# a718-noise-source.net
KiCad netlist of a schematic drawn in EAGLE
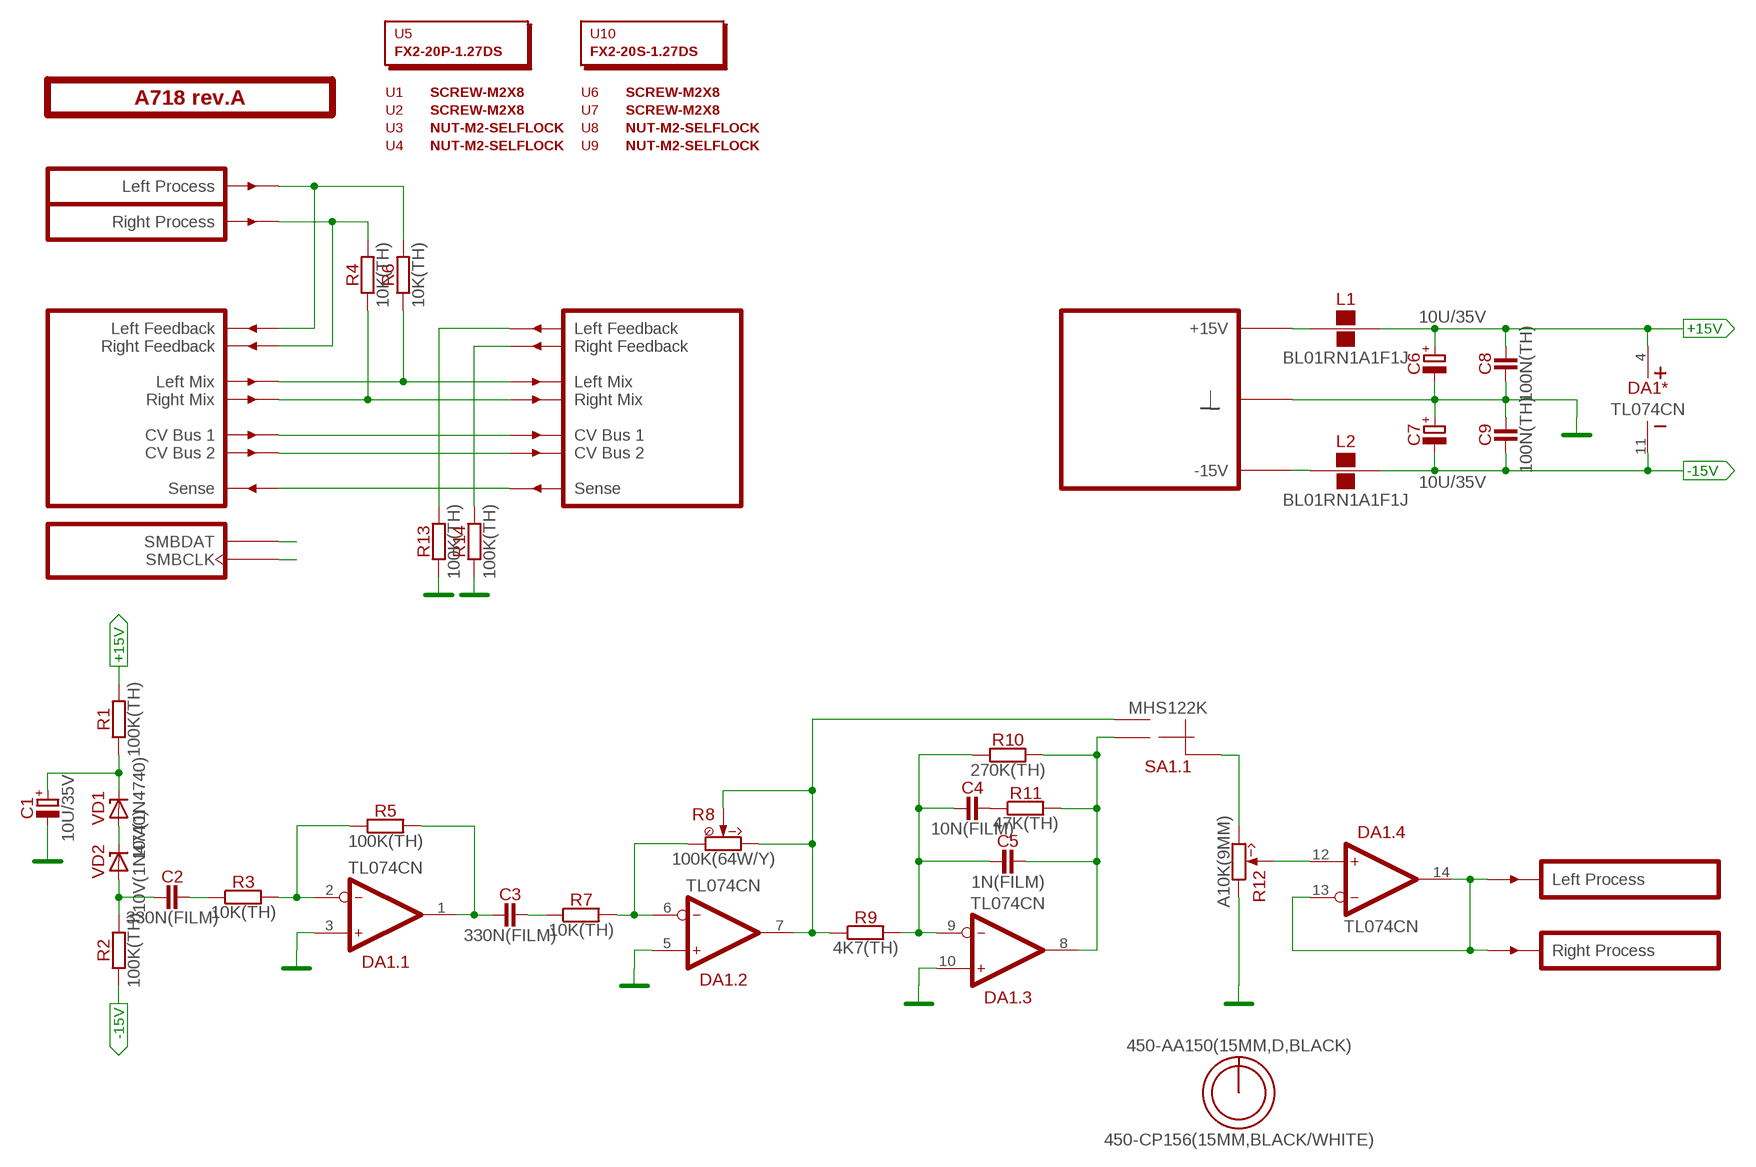
[diagram p0: schematic, sheet 1]

(export (version "E")
  (design (tool "Eeschema 10.0.6"))
  (components
    (comp (ref "C1")
      (value "10U/35V")
      (footprint "eagle-import:E2-5")
      (libsource (lib "eagle-import") (part "?10U/35V"))
    )
    (comp (ref "C2")
      (value "330N(FILM)")
      (footprint "eagle-import:C050-035X075")
      (libsource (lib "eagle-import") (part "?330N(FILM)"))
    )
    (comp (ref "C3")
      (value "330N(FILM)")
      (footprint "eagle-import:C050-035X075")
      (libsource (lib "eagle-import") (part "?330N(FILM)"))
    )
    (comp (ref "C4")
      (value "10N(FILM)")
      (footprint "eagle-import:C050-025X075")
      (libsource (lib "eagle-import") (part "?10N(FILM)"))
    )
    (comp (ref "C5")
      (value "1N(FILM)")
      (footprint "eagle-import:C050-025X075")
      (libsource (lib "eagle-import") (part "?1N(FILM)"))
    )
    (comp (ref "C6")
      (value "10U/35V")
      (footprint "eagle-import:E2-5")
      (libsource (lib "eagle-import") (part "?10U/35V"))
    )
    (comp (ref "C7")
      (value "10U/35V")
      (footprint "eagle-import:E2-5")
      (libsource (lib "eagle-import") (part "?10U/35V"))
    )
    (comp (ref "C8")
      (value "100N(TH)")
      (footprint "eagle-import:C050-024X044")
      (libsource (lib "eagle-import") (part "?100N(TH)"))
    )
    (comp (ref "C9")
      (value "100N(TH)")
      (footprint "eagle-import:C050-024X044")
      (libsource (lib "eagle-import") (part "?100N(TH)"))
    )
    (comp (ref "DA1")
      (value "TL074CN")
      (footprint "eagle-import:DIP-14")
      (libsource (lib "eagle-import") (part "TL074CN"))
    )
    (comp (ref "L1")
      (value "BL01RN1A1F1J")
      (footprint "eagle-import:BL01RN1A")
      (libsource (lib "eagle-import") (part "BL01RN1A?1F1J"))
    )
    (comp (ref "L2")
      (value "BL01RN1A1F1J")
      (footprint "eagle-import:BL01RN1A")
      (libsource (lib "eagle-import") (part "BL01RN1A?1F1J"))
    )
    (comp (ref "O1")
      (value "450-AA150(15MM,D,BLACK)")
      (footprint "eagle-import:EMPTY")
      (libsource (lib "eagle-import") (part "450-AA?150(15MM,D,BLACK)"))
    )
    (comp (ref "O2")
      (value "450-CP156(15MM,BLACK/WHITE)")
      (footprint "eagle-import:EMPTY")
      (libsource (lib "eagle-import") (part "450-C?P156(15MM,BLACK/WHITE)"))
    )
    (comp (ref "PCB1")
      (value "A718 rev.A")
      (footprint "eagle-import:ST2-BOARD-50")
      (libsource (lib "eagle-import") (part "ST2-BOARD-?50"))
    )
    (comp (ref "R1")
      (value "100K(TH)")
      (footprint "eagle-import:R-0207_10")
      (libsource (lib "eagle-import") (part "?100K(TH)"))
    )
    (comp (ref "R2")
      (value "100K(TH)")
      (footprint "eagle-import:R-0207_10")
      (libsource (lib "eagle-import") (part "?100K(TH)"))
    )
    (comp (ref "R3")
      (value "10K(TH)")
      (footprint "eagle-import:R-0207_10")
      (libsource (lib "eagle-import") (part "?10K(TH)"))
    )
    (comp (ref "R4")
      (value "10K(TH)")
      (footprint "eagle-import:R-0207_10")
      (libsource (lib "eagle-import") (part "?10K(TH)"))
    )
    (comp (ref "R5")
      (value "100K(TH)")
      (footprint "eagle-import:R-0207_10")
      (libsource (lib "eagle-import") (part "?100K(TH)"))
    )
    (comp (ref "R6")
      (value "10K(TH)")
      (footprint "eagle-import:R-0207_10")
      (libsource (lib "eagle-import") (part "?10K(TH)"))
    )
    (comp (ref "R7")
      (value "10K(TH)")
      (footprint "eagle-import:R-0207_10")
      (libsource (lib "eagle-import") (part "?10K(TH)"))
    )
    (comp (ref "R8")
      (value "100K(64W/Y)")
      (footprint "eagle-import:64W")
      (libsource (lib "eagle-import") (part "?(64W/Y)100K"))
    )
    (comp (ref "R9")
      (value "4K7(TH)")
      (footprint "eagle-import:R-0207_10")
      (libsource (lib "eagle-import") (part "?4K7(TH)"))
    )
    (comp (ref "R10")
      (value "270K(TH)")
      (footprint "eagle-import:R-0207_10")
      (libsource (lib "eagle-import") (part "?270K(TH)"))
    )
    (comp (ref "R11")
      (value "47K(TH)")
      (footprint "eagle-import:R-0207_10")
      (libsource (lib "eagle-import") (part "?47K(TH)"))
    )
    (comp (ref "R12")
      (value "A10K(9MM)")
      (footprint "eagle-import:RV09-SINGLE")
      (libsource (lib "eagle-import") (part "?A10K(9MM)"))
    )
    (comp (ref "R13")
      (value "100K(TH)")
      (footprint "eagle-import:R-0207_10")
      (libsource (lib "eagle-import") (part "?100K(TH)"))
    )
    (comp (ref "R14")
      (value "100K(TH)")
      (footprint "eagle-import:R-0207_10")
      (libsource (lib "eagle-import") (part "?100K(TH)"))
    )
    (comp (ref "SA1")
      (value "MHS122K")
      (footprint "eagle-import:APEM-MHS122K")
      (libsource (lib "eagle-import") (part "MHS122K"))
    )
    (comp (ref "U1")
      (value "SCREW-M2X8")
      (footprint "eagle-import:EMPTY")
      (libsource (lib "eagle-import") (part "?SCREW-M2X8"))
    )
    (comp (ref "U2")
      (value "SCREW-M2X8")
      (footprint "eagle-import:EMPTY")
      (libsource (lib "eagle-import") (part "?SCREW-M2X8"))
    )
    (comp (ref "U3")
      (value "NUT-M2-SELFLOCK")
      (footprint "eagle-import:EMPTY")
      (libsource (lib "eagle-import") (part "?NUT-M2-SELFLOCK"))
    )
    (comp (ref "U4")
      (value "NUT-M2-SELFLOCK")
      (footprint "eagle-import:EMPTY")
      (libsource (lib "eagle-import") (part "?NUT-M2-SELFLOCK"))
    )
    (comp (ref "U5")
      (value "FX2-20P-1.27DS")
      (footprint "eagle-import:EMPTY")
      (libsource (lib "eagle-import") (part "?FX2-20P-1.27DS"))
    )
    (comp (ref "U6")
      (value "SCREW-M2X8")
      (footprint "eagle-import:EMPTY")
      (libsource (lib "eagle-import") (part "?SCREW-M2X8"))
    )
    (comp (ref "U7")
      (value "SCREW-M2X8")
      (footprint "eagle-import:EMPTY")
      (libsource (lib "eagle-import") (part "?SCREW-M2X8"))
    )
    (comp (ref "U8")
      (value "NUT-M2-SELFLOCK")
      (footprint "eagle-import:EMPTY")
      (libsource (lib "eagle-import") (part "?NUT-M2-SELFLOCK"))
    )
    (comp (ref "U9")
      (value "NUT-M2-SELFLOCK")
      (footprint "eagle-import:EMPTY")
      (libsource (lib "eagle-import") (part "?NUT-M2-SELFLOCK"))
    )
    (comp (ref "U10")
      (value "FX2-20S-1.27DS")
      (footprint "eagle-import:EMPTY")
      (libsource (lib "eagle-import") (part "?FX2-20S-1.27DS"))
    )
    (comp (ref "VD1")
      (value "10V(1N4740)")
      (footprint "eagle-import:DO41-10")
      (libsource (lib "eagle-import") (part "?10V(1N4740)"))
    )
    (comp (ref "VD2")
      (value "10V(1N4740)")
      (footprint "eagle-import:DO41-10")
      (libsource (lib "eagle-import") (part "?10V(1N4740)"))
    )
  )
  (nets
    (net (code "1") (name "+15V") (class "Default")
      (node (ref "C6") (pin "+") (pinfunction "+_+") (pintype "passive"))
      (node (ref "C8") (pin "2") (pinfunction "2_2") (pintype "passive"))
      (node (ref "DA1") (pin "4") (pinfunction "V+_4") (pintype "power_in"))
      (node (ref "L1") (pin "2") (pinfunction "2_2") (pintype "passive"))
      (node (ref "R1") (pin "2") (pinfunction "2_2") (pintype "passive"))
    )
    (net (code "2") (name "-15V") (class "Default")
      (node (ref "C7") (pin "-") (pinfunction "-_-") (pintype "passive"))
      (node (ref "C9") (pin "1") (pinfunction "1_1") (pintype "passive"))
      (node (ref "DA1") (pin "11") (pinfunction "V-_11") (pintype "power_in"))
      (node (ref "L2") (pin "2") (pinfunction "2_2") (pintype "passive"))
      (node (ref "R2") (pin "1") (pinfunction "1_1") (pintype "passive"))
    )
    (net (code "3") (name "GND") (class "Default")
      (node (ref "C1") (pin "-") (pinfunction "-_-") (pintype "passive"))
      (node (ref "C6") (pin "-") (pinfunction "-_-") (pintype "passive"))
      (node (ref "C7") (pin "+") (pinfunction "+_+") (pintype "passive"))
      (node (ref "C8") (pin "1") (pinfunction "1_1") (pintype "passive"))
      (node (ref "C9") (pin "2") (pinfunction "2_2") (pintype "passive"))
      (node (ref "DA1") (pin "10") (pinfunction "IN+_10") (pintype "input"))
      (node (ref "DA1") (pin "3") (pinfunction "IN+_3") (pintype "input"))
      (node (ref "DA1") (pin "5") (pinfunction "IN+_5") (pintype "input"))
      (node (ref "PCB1") (pin "B4") (pinfunction "GND_B4") (pintype "bidirectional"))
      (node (ref "PCB1") (pin "B4'") (pinfunction "GND_B4'") (pintype "bidirectional"))
      (node (ref "PCB1") (pin "B5") (pinfunction "GND_B5") (pintype "bidirectional"))
      (node (ref "PCB1") (pin "B5'") (pinfunction "GND_B5'") (pintype "bidirectional"))
      (node (ref "PCB1") (pin "B6") (pinfunction "GND_B6") (pintype "bidirectional"))
      (node (ref "PCB1") (pin "B6'") (pinfunction "GND_B6'") (pintype "bidirectional"))
      (node (ref "PCB1") (pin "B7") (pinfunction "GND_B7") (pintype "bidirectional"))
      (node (ref "PCB1") (pin "B7'") (pinfunction "GND_B7'") (pintype "bidirectional"))
      (node (ref "PCB1") (pin "B8") (pinfunction "GND_B8") (pintype "bidirectional"))
      (node (ref "PCB1") (pin "B8'") (pinfunction "GND_B8'") (pintype "bidirectional"))
      (node (ref "R12") (pin "1") (pinfunction "CCW_1") (pintype "passive"))
      (node (ref "R13") (pin "1") (pinfunction "1_1") (pintype "passive"))
      (node (ref "R14") (pin "1") (pinfunction "1_1") (pintype "passive"))
    )
    (net (code "4") (name "Net-(C1-Pad+)") (class "Default")
      (node (ref "C1") (pin "+") (pinfunction "+_+") (pintype "passive"))
      (node (ref "R1") (pin "1") (pinfunction "1_1") (pintype "passive"))
      (node (ref "VD1") (pin "C") (pinfunction "C_C") (pintype "passive"))
    )
    (net (code "5") (name "Net-(C2-Pad1)") (class "Default")
      (node (ref "C2") (pin "1") (pinfunction "1_1") (pintype "passive"))
      (node (ref "R2") (pin "2") (pinfunction "2_2") (pintype "passive"))
      (node (ref "VD2") (pin "A") (pinfunction "A_A") (pintype "passive"))
    )
    (net (code "6") (name "Net-(C2-Pad2)") (class "Default")
      (node (ref "C2") (pin "2") (pinfunction "2_2") (pintype "passive"))
      (node (ref "R3") (pin "1") (pinfunction "1_1") (pintype "passive"))
    )
    (net (code "7") (name "Net-(C3-Pad2)") (class "Default")
      (node (ref "C3") (pin "2") (pinfunction "2_2") (pintype "passive"))
      (node (ref "R7") (pin "1") (pinfunction "1_1") (pintype "passive"))
    )
    (net (code "8") (name "Net-(C4-Pad2)") (class "Default")
      (node (ref "C4") (pin "2") (pinfunction "2_2") (pintype "passive"))
      (node (ref "R11") (pin "1") (pinfunction "1_1") (pintype "passive"))
    )
    (net (code "9") (name "Net-(DA1B-IN-)") (class "Default")
      (node (ref "DA1") (pin "2") (pinfunction "IN-_2") (pintype "input"))
      (node (ref "R3") (pin "2") (pinfunction "2_2") (pintype "passive"))
      (node (ref "R5") (pin "1") (pinfunction "1_1") (pintype "passive"))
    )
    (net (code "10") (name "Net-(DA1B-OUT)") (class "Default")
      (node (ref "C3") (pin "1") (pinfunction "1_1") (pintype "passive"))
      (node (ref "DA1") (pin "1") (pinfunction "OUT_1") (pintype "output"))
      (node (ref "R5") (pin "2") (pinfunction "2_2") (pintype "passive"))
    )
    (net (code "11") (name "Net-(DA1C-IN-)") (class "Default")
      (node (ref "DA1") (pin "6") (pinfunction "IN-_6") (pintype "input"))
      (node (ref "R7") (pin "2") (pinfunction "2_2") (pintype "passive"))
      (node (ref "R8") (pin "1") (pinfunction "CCW_1") (pintype "passive"))
    )
    (net (code "12") (name "Net-(DA1C-OUT)") (class "Default")
      (node (ref "DA1") (pin "7") (pinfunction "OUT_7") (pintype "output"))
      (node (ref "R8") (pin "3") (pinfunction "CW_3") (pintype "passive"))
      (node (ref "R8") (pin "S") (pinfunction "W_S") (pintype "passive"))
      (node (ref "R8") (pin "S@1") (pinfunction "W_S@1") (pintype "passive"))
      (node (ref "R9") (pin "1") (pinfunction "1_1") (pintype "passive"))
      (node (ref "SA1") (pin "2") (pinfunction "2_2") (pintype "passive"))
    )
    (net (code "13") (name "Net-(DA1D-IN-)") (class "Default")
      (node (ref "C4") (pin "1") (pinfunction "1_1") (pintype "passive"))
      (node (ref "C5") (pin "1") (pinfunction "1_1") (pintype "passive"))
      (node (ref "DA1") (pin "9") (pinfunction "IN-_9") (pintype "input"))
      (node (ref "R10") (pin "1") (pinfunction "1_1") (pintype "passive"))
      (node (ref "R9") (pin "2") (pinfunction "2_2") (pintype "passive"))
    )
    (net (code "14") (name "Net-(DA1D-OUT)") (class "Default")
      (node (ref "C5") (pin "2") (pinfunction "2_2") (pintype "passive"))
      (node (ref "DA1") (pin "8") (pinfunction "OUT_8") (pintype "output"))
      (node (ref "R10") (pin "2") (pinfunction "2_2") (pintype "passive"))
      (node (ref "R11") (pin "2") (pinfunction "2_2") (pintype "passive"))
      (node (ref "SA1") (pin "1") (pinfunction "1_1") (pintype "passive"))
    )
    (net (code "15") (name "Net-(DA1E-IN+)") (class "Default")
      (node (ref "DA1") (pin "12") (pinfunction "IN+_12") (pintype "input"))
      (node (ref "R12") (pin "2") (pinfunction "W_2") (pintype "passive"))
    )
    (net (code "16") (name "Net-(DA1E-IN-)") (class "Default")
      (node (ref "DA1") (pin "13") (pinfunction "IN-_13") (pintype "input"))
      (node (ref "DA1") (pin "14") (pinfunction "OUT_14") (pintype "output"))
      (node (ref "PCB1") (pin "BOUTL'") (pinfunction "OUTL_BOUTL'") (pintype "bidirectional"))
      (node (ref "PCB1") (pin "BOUTR'") (pinfunction "OUTR_BOUTR'") (pintype "bidirectional"))
    )
    (net (code "17") (name "Net-(L1-Pad1)") (class "Default")
      (node (ref "L1") (pin "1") (pinfunction "1_1") (pintype "passive"))
      (node (ref "PCB1") (pin "A+15") (pinfunction "P+15V_A+15") (pintype "bidirectional"))
      (node (ref "PCB1") (pin "A+15'") (pinfunction "P+15V_A+15'") (pintype "bidirectional"))
      (node (ref "PCB1") (pin "B+15") (pinfunction "P+15V_B+15") (pintype "bidirectional"))
      (node (ref "PCB1") (pin "B+15'") (pinfunction "P+15V_B+15'") (pintype "bidirectional"))
    )
    (net (code "18") (name "Net-(L2-Pad1)") (class "Default")
      (node (ref "L2") (pin "1") (pinfunction "1_1") (pintype "passive"))
      (node (ref "PCB1") (pin "A-15") (pinfunction "P-15V_A-15") (pintype "bidirectional"))
      (node (ref "PCB1") (pin "A-15'") (pinfunction "P-15V_A-15'") (pintype "bidirectional"))
      (node (ref "PCB1") (pin "B-15") (pinfunction "P-15V_B-15") (pintype "bidirectional"))
      (node (ref "PCB1") (pin "B-15'") (pinfunction "P-15V_B-15'") (pintype "bidirectional"))
    )
    (net (code "19") (name "Net-(PCB1B-INL)") (class "Default")
      (node (ref "PCB1") (pin "ALFBK") (pinfunction "LFBK_ALFBK") (pintype "bidirectional"))
      (node (ref "PCB1") (pin "BINL") (pinfunction "INL_BINL") (pintype "bidirectional"))
      (node (ref "R6") (pin "2") (pinfunction "2_2") (pintype "passive"))
    )
    (net (code "20") (name "Net-(PCB1C-INR)") (class "Default")
      (node (ref "PCB1") (pin "ARFBK") (pinfunction "RFBK_ARFBK") (pintype "bidirectional"))
      (node (ref "PCB1") (pin "BINR") (pinfunction "INR_BINR") (pintype "bidirectional"))
      (node (ref "R4") (pin "2") (pinfunction "2_2") (pintype "passive"))
    )
    (net (code "21") (name "Net-(PCB1F-CV1)") (class "Default")
      (node (ref "PCB1") (pin "ACV1") (pinfunction "CV1_ACV1") (pintype "bidirectional"))
      (node (ref "PCB1") (pin "ACV1'") (pinfunction "CV1'_ACV1'") (pintype "bidirectional"))
    )
    (net (code "22") (name "Net-(PCB1F-CV2)") (class "Default")
      (node (ref "PCB1") (pin "ACV2") (pinfunction "CV2_ACV2") (pintype "bidirectional"))
      (node (ref "PCB1") (pin "ACV2'") (pinfunction "CV2'_ACV2'") (pintype "bidirectional"))
    )
    (net (code "23") (name "Net-(PCB1F-LMIX)") (class "Default")
      (node (ref "PCB1") (pin "ALMIX") (pinfunction "LMIX_ALMIX") (pintype "bidirectional"))
      (node (ref "PCB1") (pin "ALMIX'") (pinfunction "LMIX'_ALMIX'") (pintype "bidirectional"))
      (node (ref "R6") (pin "1") (pinfunction "1_1") (pintype "passive"))
    )
    (net (code "24") (name "Net-(PCB1F-RMIX)") (class "Default")
      (node (ref "PCB1") (pin "ARMIX") (pinfunction "RMIX_ARMIX") (pintype "bidirectional"))
      (node (ref "PCB1") (pin "ARMIX'") (pinfunction "RMIX'_ARMIX'") (pintype "bidirectional"))
      (node (ref "R4") (pin "1") (pinfunction "1_1") (pintype "passive"))
    )
    (net (code "25") (name "Net-(PCB1F-SENSE)") (class "Default")
      (node (ref "PCB1") (pin "BSENSE") (pinfunction "SENSE_BSENSE") (pintype "bidirectional"))
      (node (ref "PCB1") (pin "BSENSE'") (pinfunction "SENSE'_BSENSE'") (pintype "bidirectional"))
    )
    (net (code "26") (name "Net-(PCB1G-LFBK')") (class "Default")
      (node (ref "PCB1") (pin "ALFBK'") (pinfunction "LFBK'_ALFBK'") (pintype "bidirectional"))
      (node (ref "R13") (pin "2") (pinfunction "2_2") (pintype "passive"))
    )
    (net (code "27") (name "Net-(PCB1G-RFBK')") (class "Default")
      (node (ref "PCB1") (pin "ARFBK'") (pinfunction "RFBK'_ARFBK'") (pintype "bidirectional"))
      (node (ref "R14") (pin "2") (pinfunction "2_2") (pintype "passive"))
    )
    (net (code "28") (name "Net-(PCB1H-SMBCLK-PadASMBCLK')") (class "Default")
      (node (ref "PCB1") (pin "ASMBCLK") (pinfunction "SMBCLK_ASMBCLK") (pintype "bidirectional"))
      (node (ref "PCB1") (pin "ASMBCLK'") (pinfunction "SMBCLK_ASMBCLK'") (pintype "bidirectional"))
    )
    (net (code "29") (name "Net-(PCB1H-SMBDAT-PadASMBDAT')") (class "Default")
      (node (ref "PCB1") (pin "ASMBDAT") (pinfunction "SMBDAT_ASMBDAT") (pintype "bidirectional"))
      (node (ref "PCB1") (pin "ASMBDAT'") (pinfunction "SMBDAT_ASMBDAT'") (pintype "bidirectional"))
    )
    (net (code "30") (name "Net-(R12-CW)") (class "Default")
      (node (ref "R12") (pin "3") (pinfunction "CW_3") (pintype "passive"))
      (node (ref "SA1") (pin "CMN") (pinfunction "CM_CMN") (pintype "passive"))
    )
    (net (code "31") (name "Net-(VD1-PadA)") (class "Default")
      (node (ref "VD1") (pin "A") (pinfunction "A_A") (pintype "passive"))
      (node (ref "VD2") (pin "C") (pinfunction "C_C") (pintype "passive"))
    )
  )
)
